# f-meter-1_1.net
KiCad netlist of a schematic drawn in EAGLE
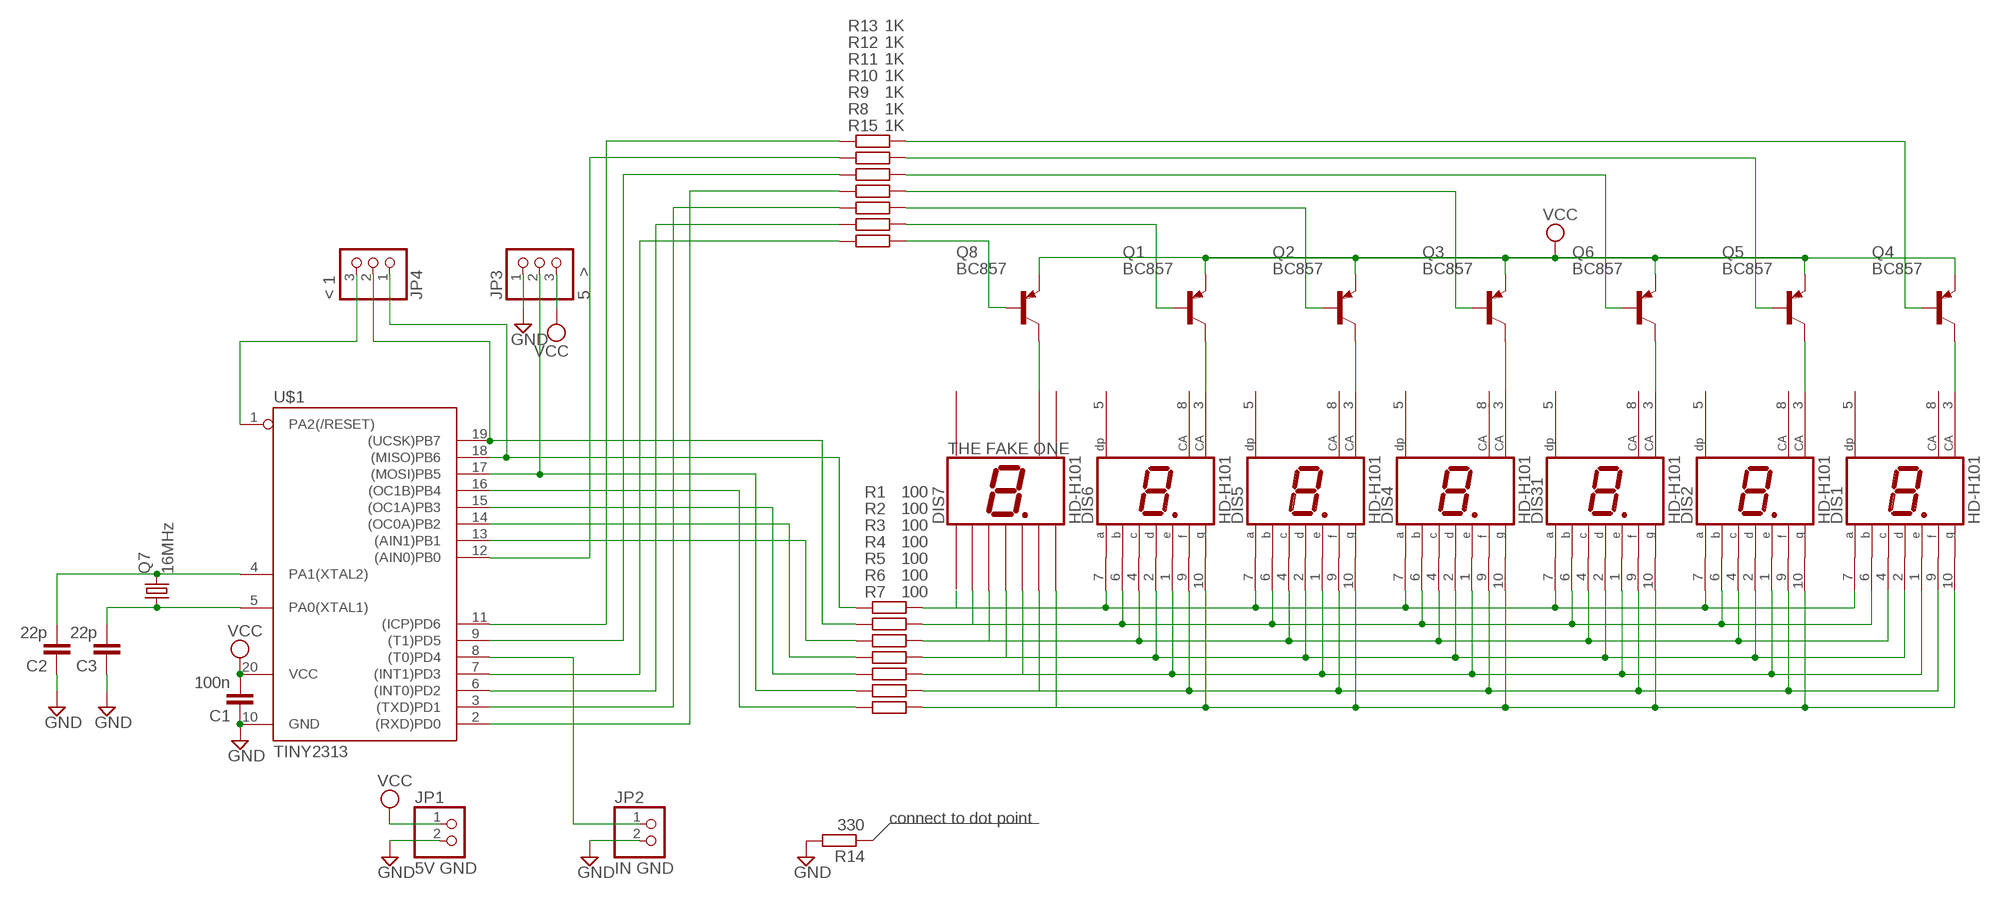
[diagram p0: schematic, sheet 1]

(export (version "E")
  (design (tool "Eeschema 10.0.6"))
  (components
    (comp (ref "C1")
      (value "100n")
      (footprint "eagle-import:C0805")
      (libsource (lib "eagle-import") (part "C-EUC0805"))
    )
    (comp (ref "C2")
      (value "22p")
      (footprint "eagle-import:C0805")
      (libsource (lib "eagle-import") (part "C-EUC0805"))
    )
    (comp (ref "C3")
      (value "22p")
      (footprint "eagle-import:C0805")
      (libsource (lib "eagle-import") (part "C-EUC0805"))
    )
    (comp (ref "DIS1")
      (value "HD-H101")
      (footprint "eagle-import:HDSP-M")
      (libsource (lib "eagle-import") (part "HD-H101"))
    )
    (comp (ref "DIS2")
      (value "HD-H101")
      (footprint "eagle-import:HDSP-M")
      (libsource (lib "eagle-import") (part "HD-H101"))
    )
    (comp (ref "DIS4")
      (value "HD-H101")
      (footprint "eagle-import:HDSP-M")
      (libsource (lib "eagle-import") (part "HD-H101"))
    )
    (comp (ref "DIS5")
      (value "HD-H101")
      (footprint "eagle-import:HDSP-M")
      (libsource (lib "eagle-import") (part "HD-H101"))
    )
    (comp (ref "DIS6")
      (value "HD-H101")
      (footprint "eagle-import:HDSP-M")
      (libsource (lib "eagle-import") (part "HD-H101"))
    )
    (comp (ref "DIS31")
      (value "HD-H101")
      (footprint "eagle-import:HDSP-M")
      (libsource (lib "eagle-import") (part "HD-H101"))
    )
    (comp (ref "JP1")
      (value "5V GND")
      (footprint "eagle-import:1X02")
      (libsource (lib "eagle-import") (part "PINHD-1X2"))
    )
    (comp (ref "JP2")
      (value "IN GND")
      (footprint "eagle-import:1X02")
      (libsource (lib "eagle-import") (part "PINHD-1X2"))
    )
    (comp (ref "JP3")
      (value "5 >")
      (footprint "eagle-import:1X03SMD_90")
      (libsource (lib "eagle-import") (part "PINHD-1X03_2.54-SMD-90°"))
    )
    (comp (ref "JP4")
      (value "< 1")
      (footprint "eagle-import:1X03SMD_90")
      (libsource (lib "eagle-import") (part "PINHD-1X03_2.54-SMD-90°"))
    )
    (comp (ref "Q1")
      (value "BC857")
      (footprint "eagle-import:SOT23-BEC")
      (libsource (lib "eagle-import") (part "BC857SMDA"))
    )
    (comp (ref "Q2")
      (value "BC857")
      (footprint "eagle-import:SOT23-BEC")
      (libsource (lib "eagle-import") (part "BC857SMDA"))
    )
    (comp (ref "Q3")
      (value "BC857")
      (footprint "eagle-import:SOT23-BEC")
      (libsource (lib "eagle-import") (part "BC857SMDA"))
    )
    (comp (ref "Q4")
      (value "BC857")
      (footprint "eagle-import:SOT23-BEC")
      (libsource (lib "eagle-import") (part "BC857SMDA"))
    )
    (comp (ref "Q5")
      (value "BC857")
      (footprint "eagle-import:SOT23-BEC")
      (libsource (lib "eagle-import") (part "BC857SMDA"))
    )
    (comp (ref "Q6")
      (value "BC857")
      (footprint "eagle-import:SOT23-BEC")
      (libsource (lib "eagle-import") (part "BC857SMDA"))
    )
    (comp (ref "Q7")
      (value "16MHz")
      (footprint "eagle-import:HC49_S")
      (libsource (lib "eagle-import") (part "CRYSTALHC49S"))
    )
    (comp (ref "Q8")
      (value "BC857")
      (footprint "eagle-import:SOT23-BEC")
      (libsource (lib "eagle-import") (part "BC857SMDA"))
    )
    (comp (ref "R1")
      (value "100")
      (footprint "eagle-import:M0805")
      (libsource (lib "eagle-import") (part "R-EU_M0805"))
    )
    (comp (ref "R2")
      (value "100")
      (footprint "eagle-import:M0805")
      (libsource (lib "eagle-import") (part "R-EU_M0805"))
    )
    (comp (ref "R3")
      (value "100")
      (footprint "eagle-import:M0805")
      (libsource (lib "eagle-import") (part "R-EU_M0805"))
    )
    (comp (ref "R4")
      (value "100")
      (footprint "eagle-import:M0805")
      (libsource (lib "eagle-import") (part "R-EU_M0805"))
    )
    (comp (ref "R5")
      (value "100")
      (footprint "eagle-import:M0805")
      (libsource (lib "eagle-import") (part "R-EU_M0805"))
    )
    (comp (ref "R6")
      (value "100")
      (footprint "eagle-import:M0805")
      (libsource (lib "eagle-import") (part "R-EU_M0805"))
    )
    (comp (ref "R7")
      (value "100")
      (footprint "eagle-import:M0805")
      (libsource (lib "eagle-import") (part "R-EU_M0805"))
    )
    (comp (ref "R8")
      (value "1K")
      (footprint "eagle-import:M0805")
      (libsource (lib "eagle-import") (part "R-EU_M0805"))
    )
    (comp (ref "R9")
      (value "1K")
      (footprint "eagle-import:M0805")
      (libsource (lib "eagle-import") (part "R-EU_M0805"))
    )
    (comp (ref "R10")
      (value "1K")
      (footprint "eagle-import:M0805")
      (libsource (lib "eagle-import") (part "R-EU_M0805"))
    )
    (comp (ref "R11")
      (value "1K")
      (footprint "eagle-import:M0805")
      (libsource (lib "eagle-import") (part "R-EU_M0805"))
    )
    (comp (ref "R12")
      (value "1K")
      (footprint "eagle-import:M0805")
      (libsource (lib "eagle-import") (part "R-EU_M0805"))
    )
    (comp (ref "R13")
      (value "1K")
      (footprint "eagle-import:M0805")
      (libsource (lib "eagle-import") (part "R-EU_M0805"))
    )
    (comp (ref "R14")
      (value "330")
      (footprint "eagle-import:M0805")
      (libsource (lib "eagle-import") (part "R-EU_M0805"))
    )
    (comp (ref "R15")
      (value "1K")
      (footprint "eagle-import:M0805")
      (libsource (lib "eagle-import") (part "R-EU_M0805"))
    )
    (comp (ref "U$1")
      (value "TINY2313")
      (footprint "eagle-import:SO20L$")
      (libsource (lib "eagle-import") (part "TINY2313-S"))
    )
  )
  (nets
    (net (code "1") (name "GND") (class "Default")
      (node (ref "C1") (pin "1") (pinfunction "1_1") (pintype "passive"))
      (node (ref "C2") (pin "1") (pinfunction "1_1") (pintype "passive"))
      (node (ref "C3") (pin "1") (pinfunction "1_1") (pintype "passive"))
      (node (ref "JP1") (pin "2") (pinfunction "2_2") (pintype "passive"))
      (node (ref "JP2") (pin "2") (pinfunction "2_2") (pintype "passive"))
      (node (ref "JP3") (pin "1") (pinfunction "1_1") (pintype "passive"))
      (node (ref "R14") (pin "2") (pinfunction "2_2") (pintype "passive"))
      (node (ref "U$1") (pin "10") (pinfunction "GND_10") (pintype "power_in"))
    )
    (net (code "2") (name "Net-(DIS1-A)") (class "Default")
      (node (ref "DIS1") (pin "7") (pinfunction "A_7") (pintype "passive"))
      (node (ref "DIS2") (pin "7") (pinfunction "A_7") (pintype "passive"))
      (node (ref "DIS31") (pin "7") (pinfunction "A_7") (pintype "passive"))
      (node (ref "DIS4") (pin "7") (pinfunction "A_7") (pintype "passive"))
      (node (ref "DIS5") (pin "7") (pinfunction "A_7") (pintype "passive"))
      (node (ref "DIS6") (pin "7") (pinfunction "A_7") (pintype "passive"))
      (node (ref "R1") (pin "2") (pinfunction "2_2") (pintype "passive"))
    )
    (net (code "3") (name "Net-(DIS1-B)") (class "Default")
      (node (ref "DIS1") (pin "6") (pinfunction "B_6") (pintype "passive"))
      (node (ref "DIS2") (pin "6") (pinfunction "B_6") (pintype "passive"))
      (node (ref "DIS31") (pin "6") (pinfunction "B_6") (pintype "passive"))
      (node (ref "DIS4") (pin "6") (pinfunction "B_6") (pintype "passive"))
      (node (ref "DIS5") (pin "6") (pinfunction "B_6") (pintype "passive"))
      (node (ref "DIS6") (pin "6") (pinfunction "B_6") (pintype "passive"))
      (node (ref "R2") (pin "2") (pinfunction "2_2") (pintype "passive"))
    )
    (net (code "4") (name "Net-(DIS1-C)") (class "Default")
      (node (ref "DIS1") (pin "4") (pinfunction "C_4") (pintype "passive"))
      (node (ref "DIS2") (pin "4") (pinfunction "C_4") (pintype "passive"))
      (node (ref "DIS31") (pin "4") (pinfunction "C_4") (pintype "passive"))
      (node (ref "DIS4") (pin "4") (pinfunction "C_4") (pintype "passive"))
      (node (ref "DIS5") (pin "4") (pinfunction "C_4") (pintype "passive"))
      (node (ref "DIS6") (pin "4") (pinfunction "C_4") (pintype "passive"))
      (node (ref "R3") (pin "2") (pinfunction "2_2") (pintype "passive"))
    )
    (net (code "5") (name "Net-(DIS1-CA-Pad3)") (class "Default")
      (node (ref "DIS1") (pin "3") (pinfunction "CA_3") (pintype "passive"))
      (node (ref "Q4") (pin "C") (pinfunction "C_C") (pintype "passive"))
    )
    (net (code "6") (name "Net-(DIS1-D)") (class "Default")
      (node (ref "DIS1") (pin "2") (pinfunction "D_2") (pintype "passive"))
      (node (ref "DIS2") (pin "2") (pinfunction "D_2") (pintype "passive"))
      (node (ref "DIS31") (pin "2") (pinfunction "D_2") (pintype "passive"))
      (node (ref "DIS4") (pin "2") (pinfunction "D_2") (pintype "passive"))
      (node (ref "DIS5") (pin "2") (pinfunction "D_2") (pintype "passive"))
      (node (ref "DIS6") (pin "2") (pinfunction "D_2") (pintype "passive"))
      (node (ref "R4") (pin "2") (pinfunction "2_2") (pintype "passive"))
    )
    (net (code "7") (name "Net-(DIS1-E)") (class "Default")
      (node (ref "DIS1") (pin "1") (pinfunction "E_1") (pintype "passive"))
      (node (ref "DIS2") (pin "1") (pinfunction "E_1") (pintype "passive"))
      (node (ref "DIS31") (pin "1") (pinfunction "E_1") (pintype "passive"))
      (node (ref "DIS4") (pin "1") (pinfunction "E_1") (pintype "passive"))
      (node (ref "DIS5") (pin "1") (pinfunction "E_1") (pintype "passive"))
      (node (ref "DIS6") (pin "1") (pinfunction "E_1") (pintype "passive"))
      (node (ref "R5") (pin "2") (pinfunction "2_2") (pintype "passive"))
    )
    (net (code "8") (name "Net-(DIS1-F)") (class "Default")
      (node (ref "DIS1") (pin "9") (pinfunction "F_9") (pintype "passive"))
      (node (ref "DIS2") (pin "9") (pinfunction "F_9") (pintype "passive"))
      (node (ref "DIS31") (pin "9") (pinfunction "F_9") (pintype "passive"))
      (node (ref "DIS4") (pin "9") (pinfunction "F_9") (pintype "passive"))
      (node (ref "DIS5") (pin "9") (pinfunction "F_9") (pintype "passive"))
      (node (ref "DIS6") (pin "9") (pinfunction "F_9") (pintype "passive"))
      (node (ref "R6") (pin "2") (pinfunction "2_2") (pintype "passive"))
    )
    (net (code "9") (name "Net-(DIS1-G)") (class "Default")
      (node (ref "DIS1") (pin "10") (pinfunction "G_10") (pintype "passive"))
      (node (ref "DIS2") (pin "10") (pinfunction "G_10") (pintype "passive"))
      (node (ref "DIS31") (pin "10") (pinfunction "G_10") (pintype "passive"))
      (node (ref "DIS4") (pin "10") (pinfunction "G_10") (pintype "passive"))
      (node (ref "DIS5") (pin "10") (pinfunction "G_10") (pintype "passive"))
      (node (ref "DIS6") (pin "10") (pinfunction "G_10") (pintype "passive"))
      (node (ref "R7") (pin "2") (pinfunction "2_2") (pintype "passive"))
    )
    (net (code "10") (name "Net-(DIS2-CA-Pad3)") (class "Default")
      (node (ref "DIS2") (pin "3") (pinfunction "CA_3") (pintype "passive"))
      (node (ref "Q5") (pin "C") (pinfunction "C_C") (pintype "passive"))
    )
    (net (code "11") (name "Net-(DIS4-CA-Pad3)") (class "Default")
      (node (ref "DIS4") (pin "3") (pinfunction "CA_3") (pintype "passive"))
      (node (ref "Q3") (pin "C") (pinfunction "C_C") (pintype "passive"))
    )
    (net (code "12") (name "Net-(DIS5-CA-Pad3)") (class "Default")
      (node (ref "DIS5") (pin "3") (pinfunction "CA_3") (pintype "passive"))
      (node (ref "Q2") (pin "C") (pinfunction "C_C") (pintype "passive"))
    )
    (net (code "13") (name "Net-(DIS6-CA-Pad3)") (class "Default")
      (node (ref "DIS6") (pin "3") (pinfunction "CA_3") (pintype "passive"))
      (node (ref "Q1") (pin "C") (pinfunction "C_C") (pintype "passive"))
    )
    (net (code "14") (name "Net-(DIS31-CA-Pad3)") (class "Default")
      (node (ref "DIS31") (pin "3") (pinfunction "CA_3") (pintype "passive"))
      (node (ref "Q6") (pin "C") (pinfunction "C_C") (pintype "passive"))
    )
    (net (code "15") (name "Net-(Q1-PadB)") (class "Default")
      (node (ref "Q1") (pin "B") (pinfunction "B_B") (pintype "passive"))
      (node (ref "R8") (pin "2") (pinfunction "2_2") (pintype "passive"))
    )
    (net (code "16") (name "Net-(Q2-PadB)") (class "Default")
      (node (ref "Q2") (pin "B") (pinfunction "B_B") (pintype "passive"))
      (node (ref "R9") (pin "2") (pinfunction "2_2") (pintype "passive"))
    )
    (net (code "17") (name "Net-(Q3-PadB)") (class "Default")
      (node (ref "Q3") (pin "B") (pinfunction "B_B") (pintype "passive"))
      (node (ref "R10") (pin "2") (pinfunction "2_2") (pintype "passive"))
    )
    (net (code "18") (name "Net-(Q4-PadB)") (class "Default")
      (node (ref "Q4") (pin "B") (pinfunction "B_B") (pintype "passive"))
      (node (ref "R13") (pin "2") (pinfunction "2_2") (pintype "passive"))
    )
    (net (code "19") (name "Net-(Q5-PadB)") (class "Default")
      (node (ref "Q5") (pin "B") (pinfunction "B_B") (pintype "passive"))
      (node (ref "R12") (pin "2") (pinfunction "2_2") (pintype "passive"))
    )
    (net (code "20") (name "Net-(Q6-PadB)") (class "Default")
      (node (ref "Q6") (pin "B") (pinfunction "B_B") (pintype "passive"))
      (node (ref "R11") (pin "2") (pinfunction "2_2") (pintype "passive"))
    )
    (net (code "21") (name "Net-(Q8-PadB)") (class "Default")
      (node (ref "Q8") (pin "B") (pinfunction "B_B") (pintype "passive"))
      (node (ref "R15") (pin "2") (pinfunction "2_2") (pintype "passive"))
    )
    (net (code "22") (name "Net-(U$1-(AIN0)PB0)") (class "Default")
      (node (ref "R12") (pin "1") (pinfunction "1_1") (pintype "passive"))
      (node (ref "U$1") (pin "12") (pinfunction "(AIN0)PB0_12") (pintype "bidirectional"))
    )
    (net (code "23") (name "Net-(U$1-(AIN1)PB1)") (class "Default")
      (node (ref "R3") (pin "1") (pinfunction "1_1") (pintype "passive"))
      (node (ref "U$1") (pin "13") (pinfunction "(AIN1)PB1_13") (pintype "bidirectional"))
    )
    (net (code "24") (name "Net-(U$1-(ICP)PD6)") (class "Default")
      (node (ref "R13") (pin "1") (pinfunction "1_1") (pintype "passive"))
      (node (ref "U$1") (pin "11") (pinfunction "(ICP)PD6_11") (pintype "bidirectional"))
    )
    (net (code "25") (name "Net-(U$1-(INT0)PD2)") (class "Default")
      (node (ref "R8") (pin "1") (pinfunction "1_1") (pintype "passive"))
      (node (ref "U$1") (pin "6") (pinfunction "(INT0)PD2_6") (pintype "bidirectional"))
    )
    (net (code "26") (name "Net-(U$1-(INT1)PD3)") (class "Default")
      (node (ref "R15") (pin "1") (pinfunction "1_1") (pintype "passive"))
      (node (ref "U$1") (pin "7") (pinfunction "(INT1)PD3_7") (pintype "bidirectional"))
    )
    (net (code "27") (name "Net-(U$1-(MISO)PB6)") (class "Default")
      (node (ref "JP4") (pin "1") (pinfunction "1_1") (pintype "passive"))
      (node (ref "R1") (pin "1") (pinfunction "1_1") (pintype "passive"))
      (node (ref "U$1") (pin "18") (pinfunction "(MISO)PB6_18") (pintype "bidirectional"))
    )
    (net (code "28") (name "Net-(U$1-(MOSI)PB5)") (class "Default")
      (node (ref "JP3") (pin "2") (pinfunction "2_2") (pintype "passive"))
      (node (ref "R6") (pin "1") (pinfunction "1_1") (pintype "passive"))
      (node (ref "U$1") (pin "17") (pinfunction "(MOSI)PB5_17") (pintype "bidirectional"))
    )
    (net (code "29") (name "Net-(U$1-(OC0A)PB2)") (class "Default")
      (node (ref "R4") (pin "1") (pinfunction "1_1") (pintype "passive"))
      (node (ref "U$1") (pin "14") (pinfunction "(OC0A)PB2_14") (pintype "bidirectional"))
    )
    (net (code "30") (name "Net-(U$1-(OC1A)PB3)") (class "Default")
      (node (ref "R5") (pin "1") (pinfunction "1_1") (pintype "passive"))
      (node (ref "U$1") (pin "15") (pinfunction "(OC1A)PB3_15") (pintype "bidirectional"))
    )
    (net (code "31") (name "Net-(U$1-(OC1B)PB4)") (class "Default")
      (node (ref "R7") (pin "1") (pinfunction "1_1") (pintype "passive"))
      (node (ref "U$1") (pin "16") (pinfunction "(OC1B)PB4_16") (pintype "bidirectional"))
    )
    (net (code "32") (name "Net-(U$1-(RXD)PD0)") (class "Default")
      (node (ref "R10") (pin "1") (pinfunction "1_1") (pintype "passive"))
      (node (ref "U$1") (pin "2") (pinfunction "(RXD)PD0_2") (pintype "bidirectional"))
    )
    (net (code "33") (name "Net-(U$1-(T0)PD4)") (class "Default")
      (node (ref "JP2") (pin "1") (pinfunction "1_1") (pintype "passive"))
      (node (ref "U$1") (pin "8") (pinfunction "(T0)PD4_8") (pintype "bidirectional"))
    )
    (net (code "34") (name "Net-(U$1-(T1)PD5)") (class "Default")
      (node (ref "R11") (pin "1") (pinfunction "1_1") (pintype "passive"))
      (node (ref "U$1") (pin "9") (pinfunction "(T1)PD5_9") (pintype "bidirectional"))
    )
    (net (code "35") (name "Net-(U$1-(TXD)PD1)") (class "Default")
      (node (ref "R9") (pin "1") (pinfunction "1_1") (pintype "passive"))
      (node (ref "U$1") (pin "3") (pinfunction "(TXD)PD1_3") (pintype "bidirectional"))
    )
    (net (code "36") (name "Net-(U$1-(UCSK)PB7)") (class "Default")
      (node (ref "JP4") (pin "2") (pinfunction "2_2") (pintype "passive"))
      (node (ref "R2") (pin "1") (pinfunction "1_1") (pintype "passive"))
      (node (ref "U$1") (pin "19") (pinfunction "(UCSK)PB7_19") (pintype "bidirectional"))
    )
    (net (code "37") (name "Net-(U$1-PA0(XTAL1))") (class "Default")
      (node (ref "C3") (pin "2") (pinfunction "2_2") (pintype "passive"))
      (node (ref "Q7") (pin "1") (pinfunction "1_1") (pintype "passive"))
      (node (ref "U$1") (pin "5") (pinfunction "PA0(XTAL1)_5") (pintype "bidirectional"))
    )
    (net (code "38") (name "Net-(U$1-PA1(XTAL2))") (class "Default")
      (node (ref "C2") (pin "2") (pinfunction "2_2") (pintype "passive"))
      (node (ref "Q7") (pin "2") (pinfunction "2_2") (pintype "passive"))
      (node (ref "U$1") (pin "4") (pinfunction "PA1(XTAL2)_4") (pintype "bidirectional"))
    )
    (net (code "39") (name "Net-(U$1-PA2({slash}RESET))") (class "Default")
      (node (ref "JP4") (pin "3") (pinfunction "3_3") (pintype "passive"))
      (node (ref "U$1") (pin "1") (pinfunction "PA2(/RESET)_1") (pintype "input"))
    )
    (net (code "40") (name "VCC") (class "Default")
      (node (ref "C1") (pin "2") (pinfunction "2_2") (pintype "passive"))
      (node (ref "JP1") (pin "1") (pinfunction "1_1") (pintype "passive"))
      (node (ref "JP3") (pin "3") (pinfunction "3_3") (pintype "passive"))
      (node (ref "Q1") (pin "E") (pinfunction "E_E") (pintype "passive"))
      (node (ref "Q2") (pin "E") (pinfunction "E_E") (pintype "passive"))
      (node (ref "Q3") (pin "E") (pinfunction "E_E") (pintype "passive"))
      (node (ref "Q4") (pin "E") (pinfunction "E_E") (pintype "passive"))
      (node (ref "Q5") (pin "E") (pinfunction "E_E") (pintype "passive"))
      (node (ref "Q6") (pin "E") (pinfunction "E_E") (pintype "passive"))
      (node (ref "Q8") (pin "E") (pinfunction "E_E") (pintype "passive"))
      (node (ref "U$1") (pin "20") (pinfunction "VCC_20") (pintype "power_in"))
    )
    (net (code "41") (name "unconnected-(DIS1-CA-Pad8)") (class "Default")
      (node (ref "DIS1") (pin "8") (pinfunction "CA_8") (pintype "passive"))
    )
    (net (code "42") (name "unconnected-(DIS1-DP-Pad5)") (class "Default")
      (node (ref "DIS1") (pin "5") (pinfunction "DP_5") (pintype "passive"))
    )
    (net (code "43") (name "unconnected-(DIS2-CA-Pad8)") (class "Default")
      (node (ref "DIS2") (pin "8") (pinfunction "CA_8") (pintype "passive"))
    )
    (net (code "44") (name "unconnected-(DIS2-DP-Pad5)") (class "Default")
      (node (ref "DIS2") (pin "5") (pinfunction "DP_5") (pintype "passive"))
    )
    (net (code "45") (name "unconnected-(DIS4-CA-Pad8)") (class "Default")
      (node (ref "DIS4") (pin "8") (pinfunction "CA_8") (pintype "passive"))
    )
    (net (code "46") (name "unconnected-(DIS4-DP-Pad5)") (class "Default")
      (node (ref "DIS4") (pin "5") (pinfunction "DP_5") (pintype "passive"))
    )
    (net (code "47") (name "unconnected-(DIS5-CA-Pad8)") (class "Default")
      (node (ref "DIS5") (pin "8") (pinfunction "CA_8") (pintype "passive"))
    )
    (net (code "48") (name "unconnected-(DIS5-DP-Pad5)") (class "Default")
      (node (ref "DIS5") (pin "5") (pinfunction "DP_5") (pintype "passive"))
    )
    (net (code "49") (name "unconnected-(DIS6-CA-Pad8)") (class "Default")
      (node (ref "DIS6") (pin "8") (pinfunction "CA_8") (pintype "passive"))
    )
    (net (code "50") (name "unconnected-(DIS6-DP-Pad5)") (class "Default")
      (node (ref "DIS6") (pin "5") (pinfunction "DP_5") (pintype "passive"))
    )
    (net (code "51") (name "unconnected-(DIS31-CA-Pad8)") (class "Default")
      (node (ref "DIS31") (pin "8") (pinfunction "CA_8") (pintype "passive"))
    )
    (net (code "52") (name "unconnected-(DIS31-DP-Pad5)") (class "Default")
      (node (ref "DIS31") (pin "5") (pinfunction "DP_5") (pintype "passive"))
    )
    (net (code "53") (name "unconnected-(Q8-PadC)") (class "Default")
      (node (ref "Q8") (pin "C") (pinfunction "C_C") (pintype "passive"))
    )
    (net (code "54") (name "unconnected-(R14-Pad1)") (class "Default")
      (node (ref "R14") (pin "1") (pinfunction "1_1") (pintype "passive"))
    )
  )
)
